# FT231XS_USB_to_Serial.net
KiCad netlist of a schematic drawn in EAGLE
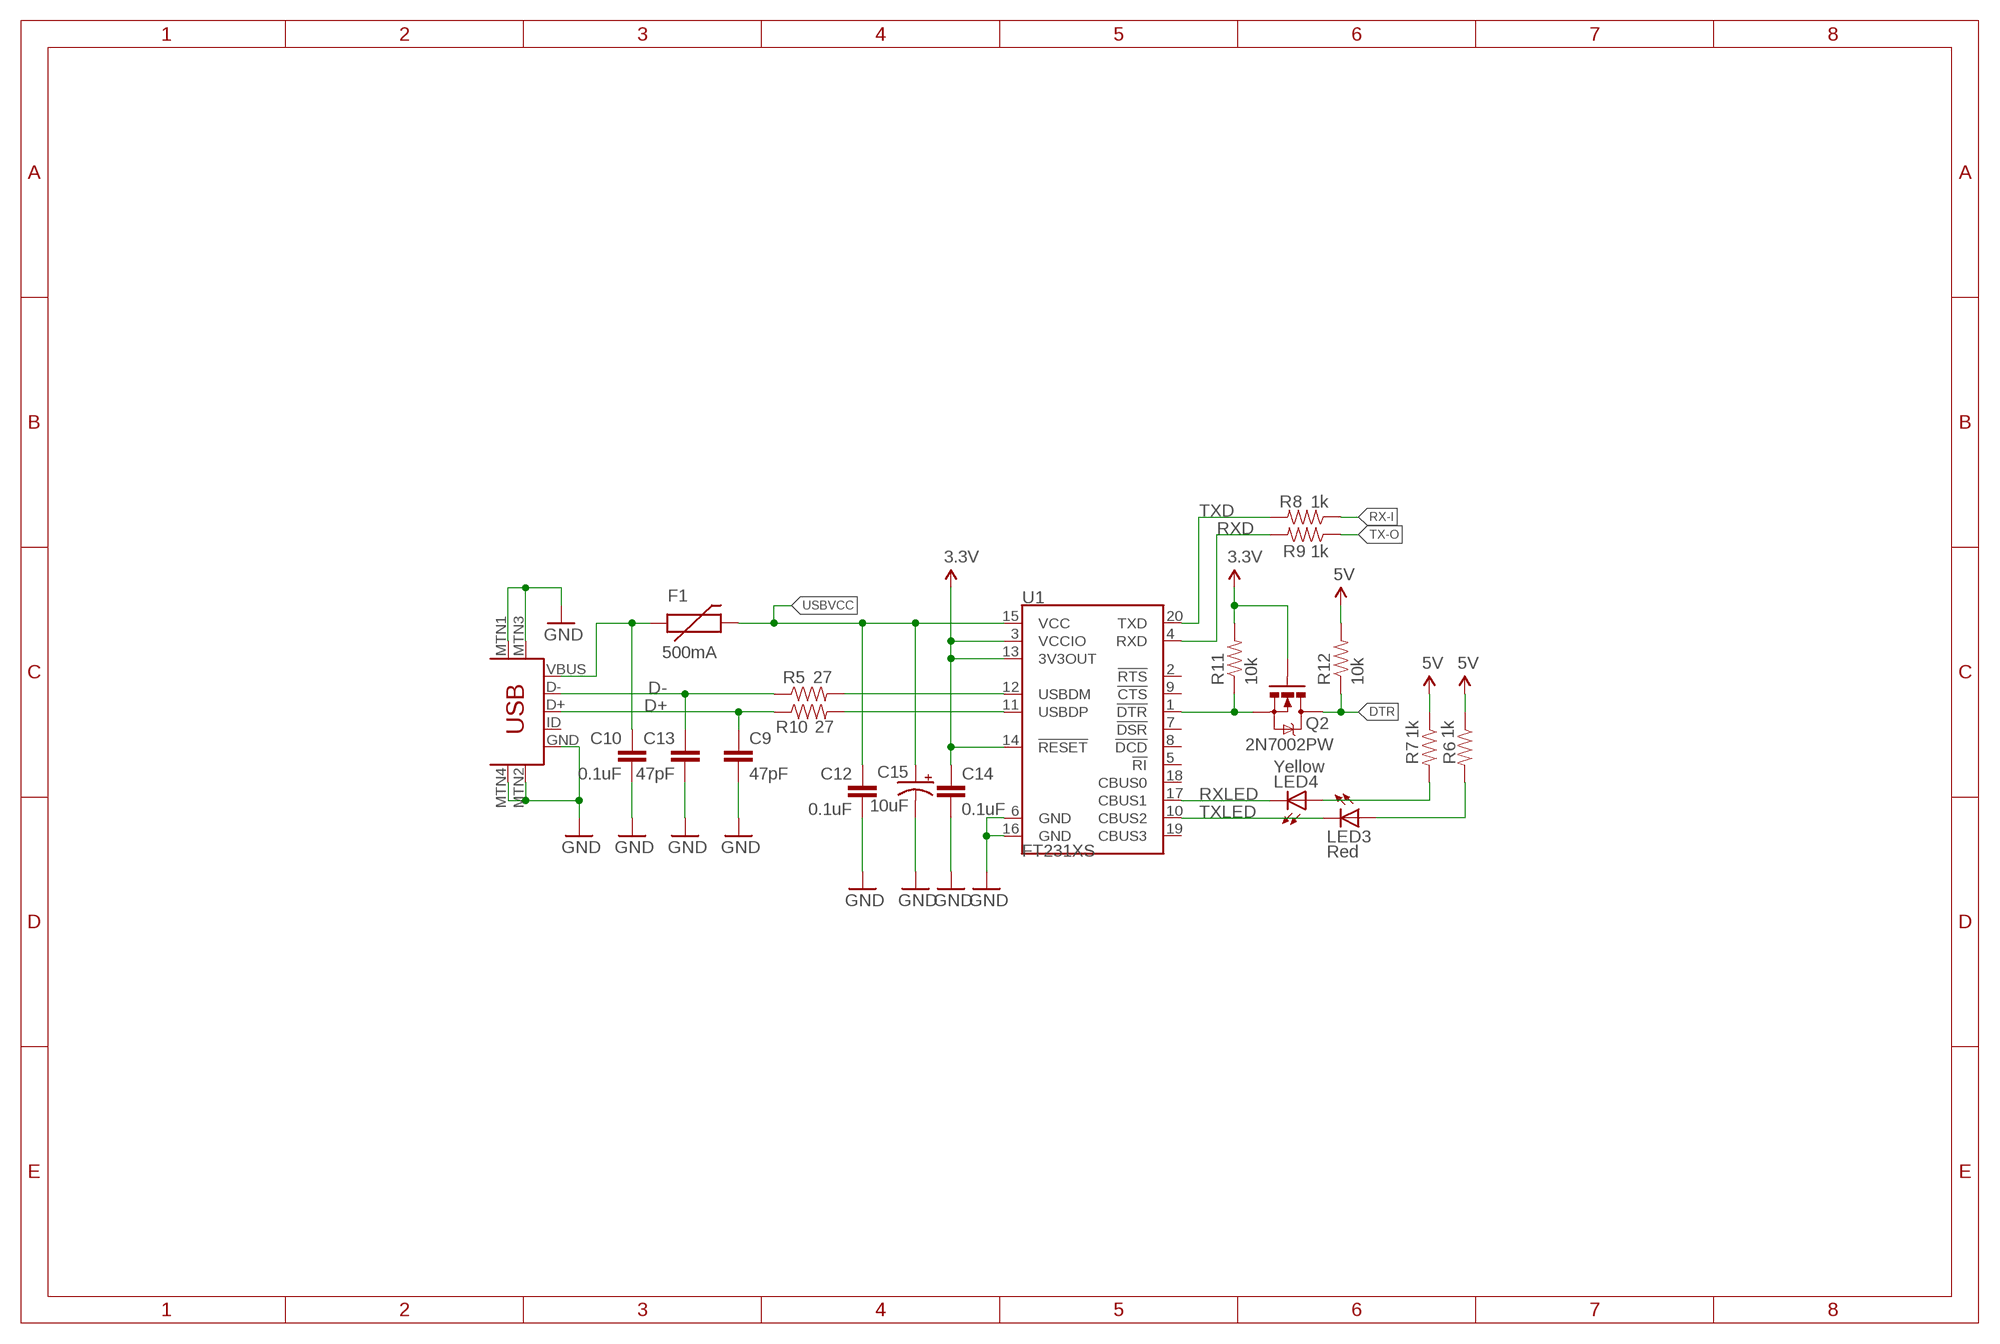
[diagram p0: schematic, sheet 1]

(export (version "E")
  (design (tool "Eeschema 10.0.6"))
  (components
    (comp (ref "C9")
      (value "47pF")
      (footprint "eagle-import:0603-CAP")
      (libsource (lib "eagle-import") (part "47PF-50V-5%(0603)"))
    )
    (comp (ref "C10")
      (value "0.1uF")
      (footprint "eagle-import:0603-CAP")
      (libsource (lib "eagle-import") (part "CAP0603-CAP"))
    )
    (comp (ref "C12")
      (value "0.1uF")
      (footprint "eagle-import:0603-CAP")
      (libsource (lib "eagle-import") (part "CAP0603-CAP"))
    )
    (comp (ref "C13")
      (value "47pF")
      (footprint "eagle-import:0603-CAP")
      (libsource (lib "eagle-import") (part "47PF-50V-5%(0603)"))
    )
    (comp (ref "C14")
      (value "0.1uF")
      (footprint "eagle-import:0603-CAP")
      (libsource (lib "eagle-import") (part "CAP0603-CAP"))
    )
    (comp (ref "C15")
      (value "10uF")
      (footprint "eagle-import:EIA3216")
      (libsource (lib "eagle-import") (part "CAP_POL1206"))
    )
    (comp (ref "F1")
      (value "500mA")
      (footprint "eagle-import:PTC-1206")
      (libsource (lib "eagle-import") (part "PTCSMD"))
    )
    (comp (ref "LED3")
      (value "Red")
      (footprint "eagle-import:LED-1206-NO_SILK")
      (libsource (lib "eagle-import") (part "LED1206-NS"))
    )
    (comp (ref "LED4")
      (value "Yellow")
      (footprint "eagle-import:LED-1206-NO_SILK")
      (libsource (lib "eagle-import") (part "LED1206-NS"))
    )
    (comp (ref "Q2")
      (value "2N7002PW")
      (footprint "eagle-import:SOT323")
      (libsource (lib "eagle-import") (part "MOSFET-NCHANNEL2N7002PW"))
    )
    (comp (ref "R5")
      (value "27")
      (footprint "eagle-import:0603-RES")
      (libsource (lib "eagle-import") (part "SparkFun-Resistors_RESISTOR0603-RES"))
    )
    (comp (ref "R6")
      (value "1k")
      (footprint "eagle-import:0603-RES")
      (libsource (lib "eagle-import") (part "RESISTOR0603-RES"))
    )
    (comp (ref "R7")
      (value "1k")
      (footprint "eagle-import:0603-RES")
      (libsource (lib "eagle-import") (part "RESISTOR0603-RES"))
    )
    (comp (ref "R8")
      (value "1k")
      (footprint "eagle-import:0603-RES")
      (libsource (lib "eagle-import") (part "RESISTOR0603-RES"))
    )
    (comp (ref "R9")
      (value "1k")
      (footprint "eagle-import:0603-RES")
      (libsource (lib "eagle-import") (part "RESISTOR0603-RES"))
    )
    (comp (ref "R10")
      (value "27")
      (footprint "eagle-import:0603-RES")
      (libsource (lib "eagle-import") (part "SparkFun-Resistors_RESISTOR0603-RES"))
    )
    (comp (ref "R11")
      (value "10k")
      (footprint "eagle-import:0603-RES")
      (libsource (lib "eagle-import") (part "RESISTOR0603-RES"))
    )
    (comp (ref "R12")
      (value "10k")
      (footprint "eagle-import:0603-RES")
      (libsource (lib "eagle-import") (part "RESISTOR0603-RES"))
    )
    (comp (ref "U$13")
      (value "USB-MINIB-5PIN")
      (footprint "eagle-import:USB-MINIB")
      (libsource (lib "eagle-import") (part "USB-MINIB-5PIN"))
    )
    (comp (ref "U1")
      (value "FT231XS")
      (footprint "eagle-import:SSOP20_L")
      (libsource (lib "eagle-import") (part "FT231XS"))
    )
  )
  (nets
    (net (code "1") (name "/D+") (class "Default")
      (node (ref "C9") (pin "1") (pinfunction "1_1") (pintype "passive"))
      (node (ref "R10") (pin "1") (pinfunction "1_1") (pintype "passive"))
      (node (ref "U$13") (pin "D+") (pinfunction "D+_D+") (pintype "bidirectional"))
    )
    (net (code "2") (name "/D-") (class "Default")
      (node (ref "C13") (pin "1") (pinfunction "1_1") (pintype "passive"))
      (node (ref "R5") (pin "1") (pinfunction "1_1") (pintype "passive"))
      (node (ref "U$13") (pin "D-") (pinfunction "D-_D-") (pintype "bidirectional"))
    )
    (net (code "3") (name "/RXD") (class "Default")
      (node (ref "R9") (pin "2") (pinfunction "2_2") (pintype "passive"))
      (node (ref "U1") (pin "4") (pinfunction "RXD_4") (pintype "bidirectional"))
    )
    (net (code "4") (name "/RXLED") (class "Default")
      (node (ref "LED4") (pin "C") (pinfunction "C_C") (pintype "passive"))
      (node (ref "U1") (pin "17") (pinfunction "CBUS1_17") (pintype "bidirectional"))
    )
    (net (code "5") (name "/TXD") (class "Default")
      (node (ref "R8") (pin "2") (pinfunction "2_2") (pintype "passive"))
      (node (ref "U1") (pin "20") (pinfunction "TXD_20") (pintype "bidirectional"))
    )
    (net (code "6") (name "/TXLED") (class "Default")
      (node (ref "LED3") (pin "C") (pinfunction "C_C") (pintype "passive"))
      (node (ref "U1") (pin "10") (pinfunction "CBUS2_10") (pintype "bidirectional"))
    )
    (net (code "7") (name "3.3V") (class "Default")
      (node (ref "C14") (pin "1") (pinfunction "1_1") (pintype "passive"))
      (node (ref "Q2") (pin "1") (pinfunction "G_1") (pintype "passive"))
      (node (ref "R11") (pin "2") (pinfunction "2_2") (pintype "passive"))
      (node (ref "U1") (pin "13") (pinfunction "3V3OUT_13") (pintype "bidirectional"))
      (node (ref "U1") (pin "14") (pinfunction "~{RESET}_14") (pintype "bidirectional"))
      (node (ref "U1") (pin "3") (pinfunction "VCCIO_3") (pintype "bidirectional"))
    )
    (net (code "8") (name "5V") (class "Default")
      (node (ref "R12") (pin "2") (pinfunction "2_2") (pintype "passive"))
      (node (ref "R6") (pin "1") (pinfunction "1_1") (pintype "passive"))
      (node (ref "R7") (pin "1") (pinfunction "1_1") (pintype "passive"))
    )
    (net (code "9") (name "DTR") (class "Default")
      (node (ref "Q2") (pin "3") (pinfunction "D_3") (pintype "passive"))
      (node (ref "R12") (pin "1") (pinfunction "1_1") (pintype "passive"))
    )
    (net (code "10") (name "GND") (class "Default")
      (node (ref "C10") (pin "2") (pinfunction "2_2") (pintype "passive"))
      (node (ref "C12") (pin "2") (pinfunction "2_2") (pintype "passive"))
      (node (ref "C13") (pin "2") (pinfunction "2_2") (pintype "passive"))
      (node (ref "C14") (pin "2") (pinfunction "2_2") (pintype "passive"))
      (node (ref "C15") (pin "C") (pinfunction "-_C") (pintype "passive"))
      (node (ref "C9") (pin "2") (pinfunction "2_2") (pintype "passive"))
      (node (ref "U$13") (pin "GND") (pinfunction "GND_GND") (pintype "bidirectional"))
      (node (ref "U$13") (pin "MTN1") (pinfunction "MTN2_MTN1") (pintype "bidirectional"))
      (node (ref "U$13") (pin "MTN2") (pinfunction "MTN3_MTN2") (pintype "bidirectional"))
      (node (ref "U$13") (pin "MTN3") (pinfunction "MTN1_MTN3") (pintype "bidirectional"))
      (node (ref "U$13") (pin "MTN4") (pinfunction "MTN4_MTN4") (pintype "bidirectional"))
      (node (ref "U1") (pin "16") (pinfunction "GND_16") (pintype "bidirectional"))
      (node (ref "U1") (pin "6") (pinfunction "GND_6") (pintype "bidirectional"))
    )
    (net (code "11") (name "Net-(C10-Pad1)") (class "Default")
      (node (ref "C10") (pin "1") (pinfunction "1_1") (pintype "passive"))
      (node (ref "F1") (pin "1") (pinfunction "1_1") (pintype "bidirectional"))
      (node (ref "U$13") (pin "VBUS") (pinfunction "VBUS_VBUS") (pintype "bidirectional"))
    )
    (net (code "12") (name "Net-(LED3-PadA)") (class "Default")
      (node (ref "LED3") (pin "A") (pinfunction "A_A") (pintype "passive"))
      (node (ref "R6") (pin "2") (pinfunction "2_2") (pintype "passive"))
    )
    (net (code "13") (name "Net-(LED4-PadA)") (class "Default")
      (node (ref "LED4") (pin "A") (pinfunction "A_A") (pintype "passive"))
      (node (ref "R7") (pin "2") (pinfunction "2_2") (pintype "passive"))
    )
    (net (code "14") (name "Net-(Q2-S)") (class "Default")
      (node (ref "Q2") (pin "2") (pinfunction "S_2") (pintype "passive"))
      (node (ref "R11") (pin "1") (pinfunction "1_1") (pintype "passive"))
      (node (ref "U1") (pin "1") (pinfunction "~{DTR}_1") (pintype "bidirectional"))
    )
    (net (code "15") (name "Net-(U1-USBDM)") (class "Default")
      (node (ref "R5") (pin "2") (pinfunction "2_2") (pintype "passive"))
      (node (ref "U1") (pin "12") (pinfunction "USBDM_12") (pintype "bidirectional"))
    )
    (net (code "16") (name "Net-(U1-USBDP)") (class "Default")
      (node (ref "R10") (pin "2") (pinfunction "2_2") (pintype "passive"))
      (node (ref "U1") (pin "11") (pinfunction "USBDP_11") (pintype "bidirectional"))
    )
    (net (code "17") (name "RX-I") (class "Default")
      (node (ref "R8") (pin "1") (pinfunction "1_1") (pintype "passive"))
    )
    (net (code "18") (name "TX-O") (class "Default")
      (node (ref "R9") (pin "1") (pinfunction "1_1") (pintype "passive"))
    )
    (net (code "19") (name "USBVCC") (class "Default")
      (node (ref "C12") (pin "1") (pinfunction "1_1") (pintype "passive"))
      (node (ref "C15") (pin "A") (pinfunction "+_A") (pintype "passive"))
      (node (ref "F1") (pin "2") (pinfunction "2_2") (pintype "bidirectional"))
      (node (ref "U1") (pin "15") (pinfunction "VCC_15") (pintype "bidirectional"))
    )
    (net (code "20") (name "unconnected-(U$13-PadID)") (class "Default")
      (node (ref "U$13") (pin "ID") (pinfunction "ID_ID") (pintype "bidirectional"))
    )
    (net (code "21") (name "unconnected-(U1-CBUS0-Pad18)") (class "Default")
      (node (ref "U1") (pin "18") (pinfunction "CBUS0_18") (pintype "bidirectional"))
    )
    (net (code "22") (name "unconnected-(U1-CBUS3-Pad19)") (class "Default")
      (node (ref "U1") (pin "19") (pinfunction "CBUS3_19") (pintype "bidirectional"))
    )
    (net (code "23") (name "unconnected-(U1-~{CTS}-Pad9)") (class "Default")
      (node (ref "U1") (pin "9") (pinfunction "~{CTS}_9") (pintype "bidirectional"))
    )
    (net (code "24") (name "unconnected-(U1-~{DCD}-Pad8)") (class "Default")
      (node (ref "U1") (pin "8") (pinfunction "~{DCD}_8") (pintype "bidirectional"))
    )
    (net (code "25") (name "unconnected-(U1-~{DSR}-Pad7)") (class "Default")
      (node (ref "U1") (pin "7") (pinfunction "~{DSR}_7") (pintype "bidirectional"))
    )
    (net (code "26") (name "unconnected-(U1-~{RI}-Pad5)") (class "Default")
      (node (ref "U1") (pin "5") (pinfunction "~{RI}_5") (pintype "bidirectional"))
    )
    (net (code "27") (name "unconnected-(U1-~{RTS}-Pad2)") (class "Default")
      (node (ref "U1") (pin "2") (pinfunction "~{RTS}_2") (pintype "bidirectional"))
    )
  )
)
